# RF-antenna.net
KiCad netlist of a schematic drawn in EAGLE
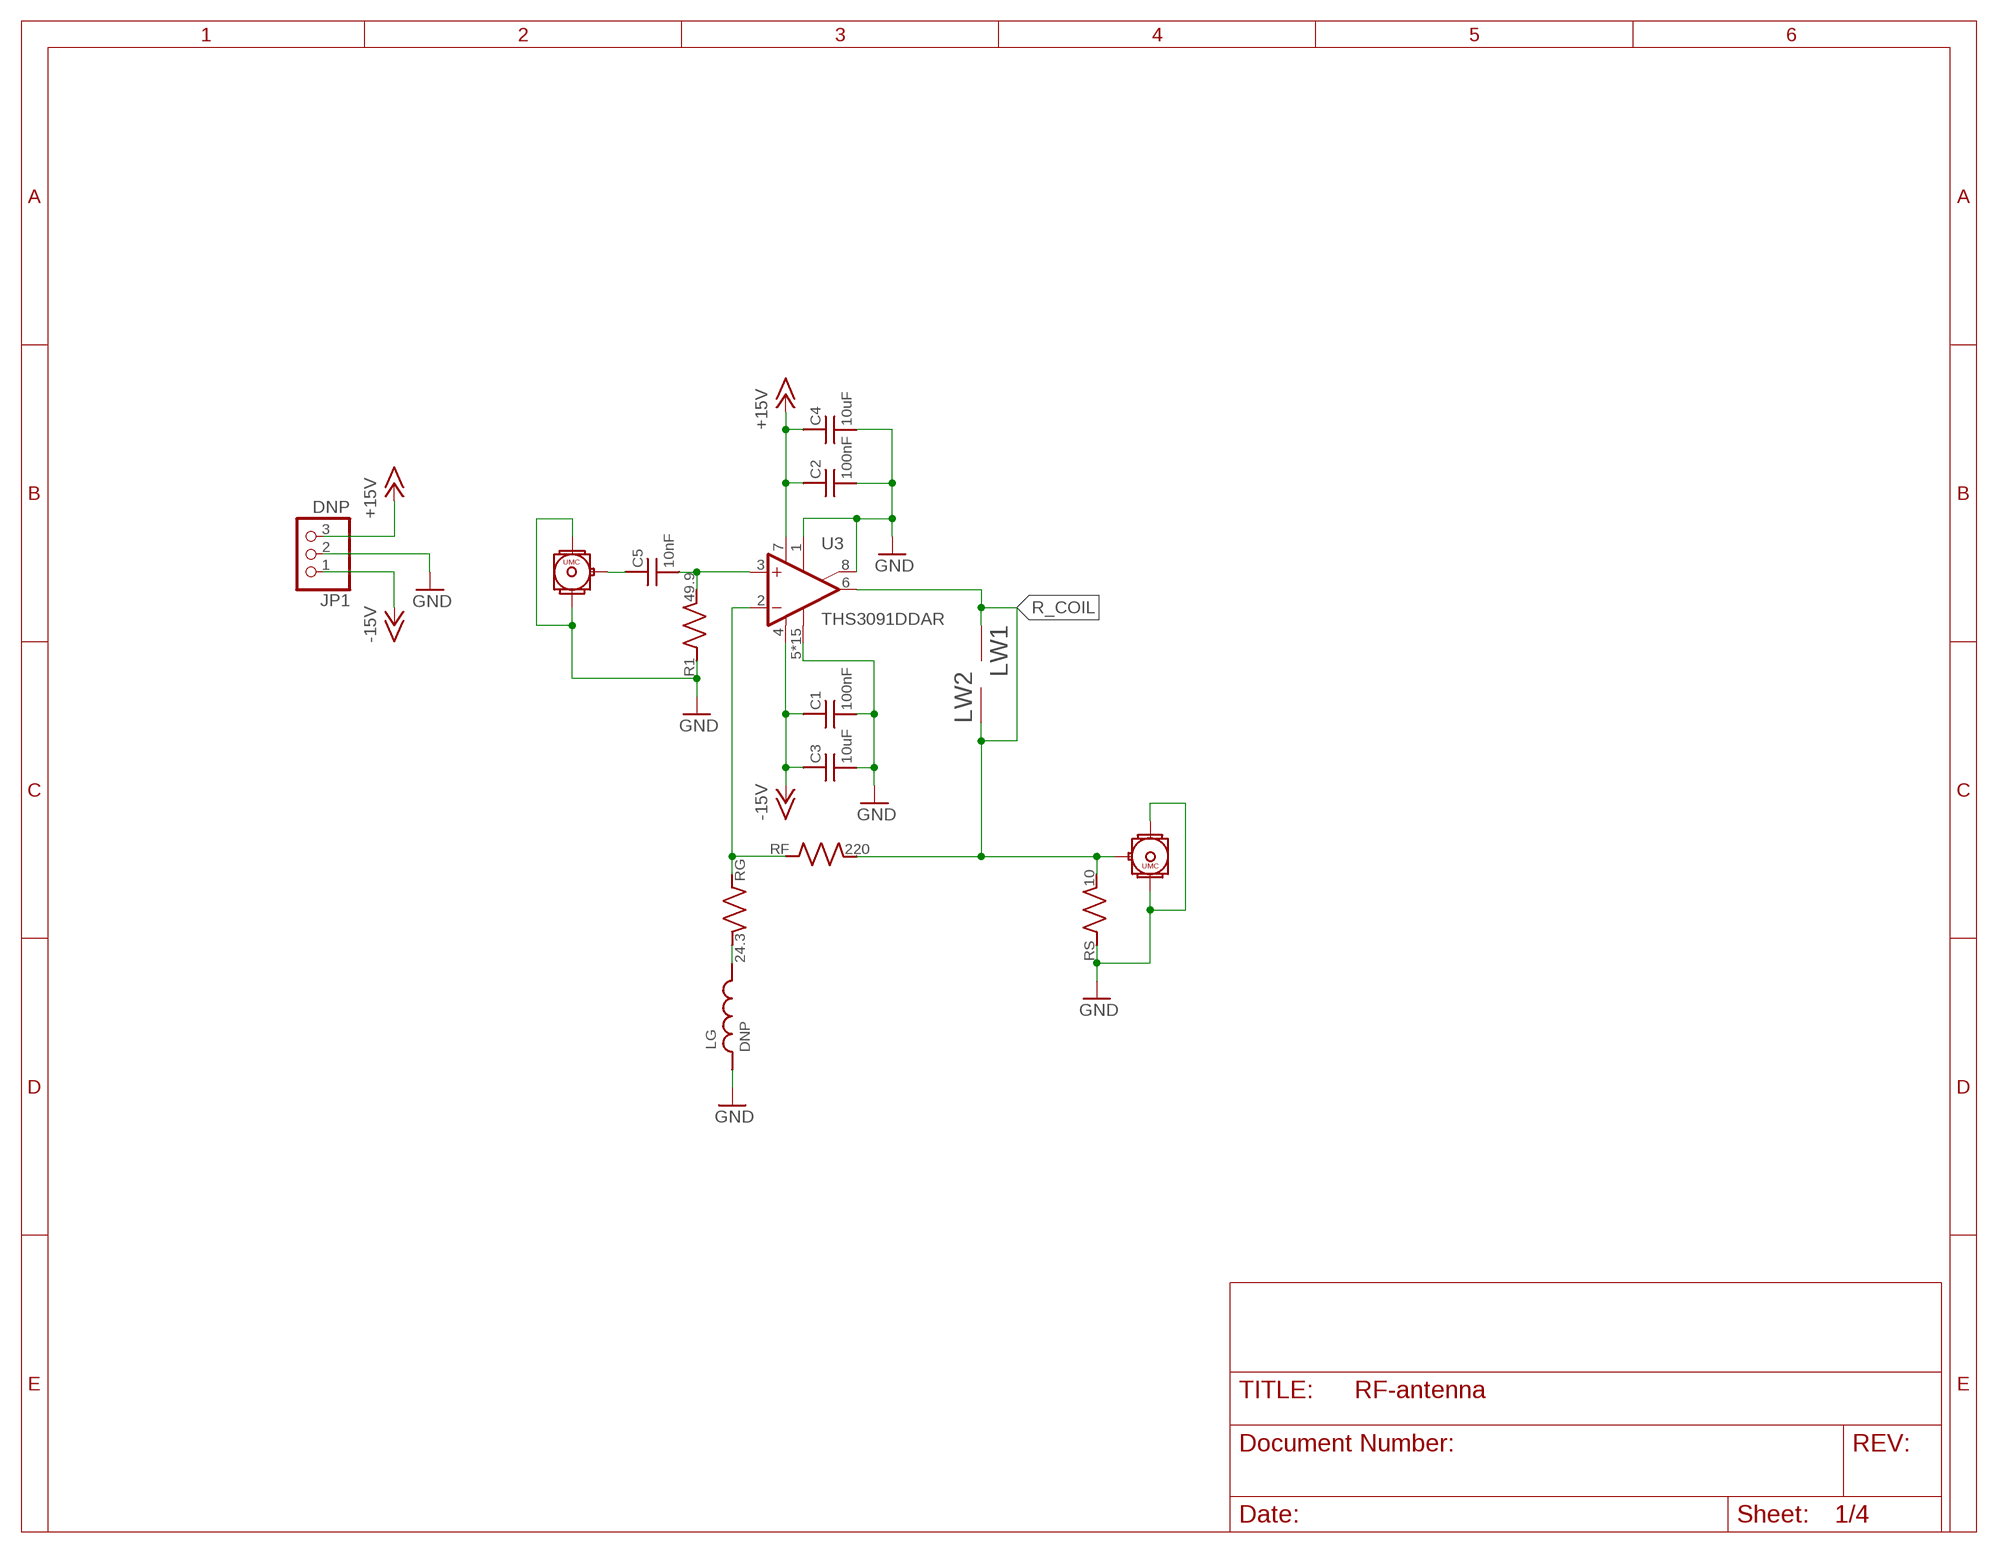
[diagram p0: schematic, sheet 1]
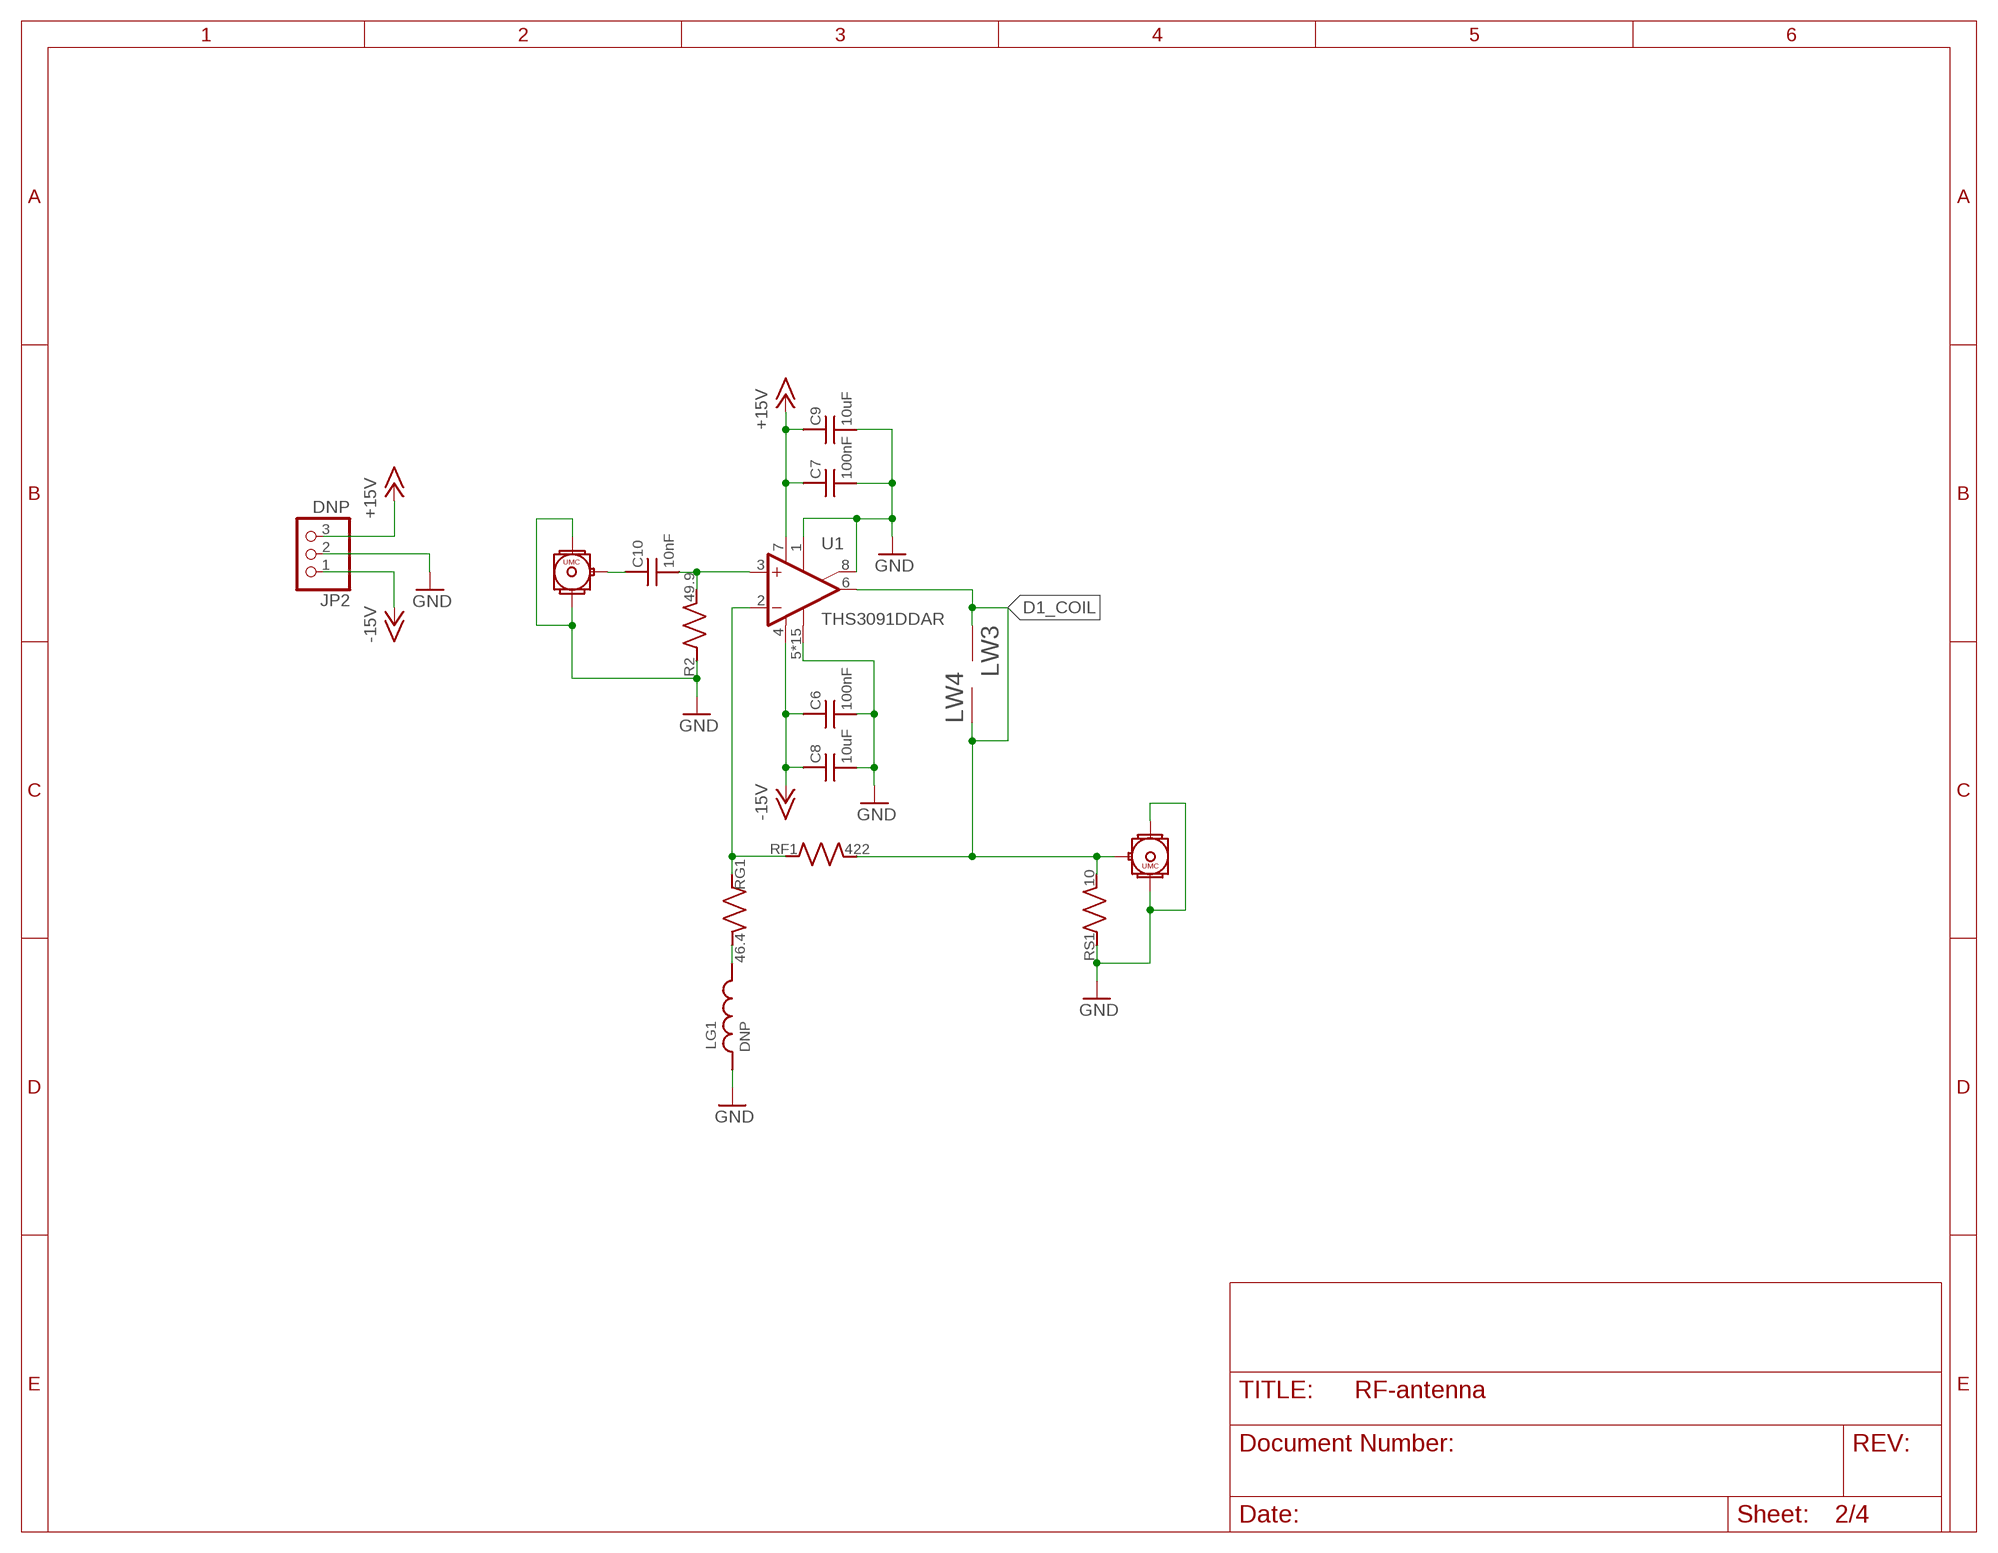
[diagram p1: schematic, sheet 2]
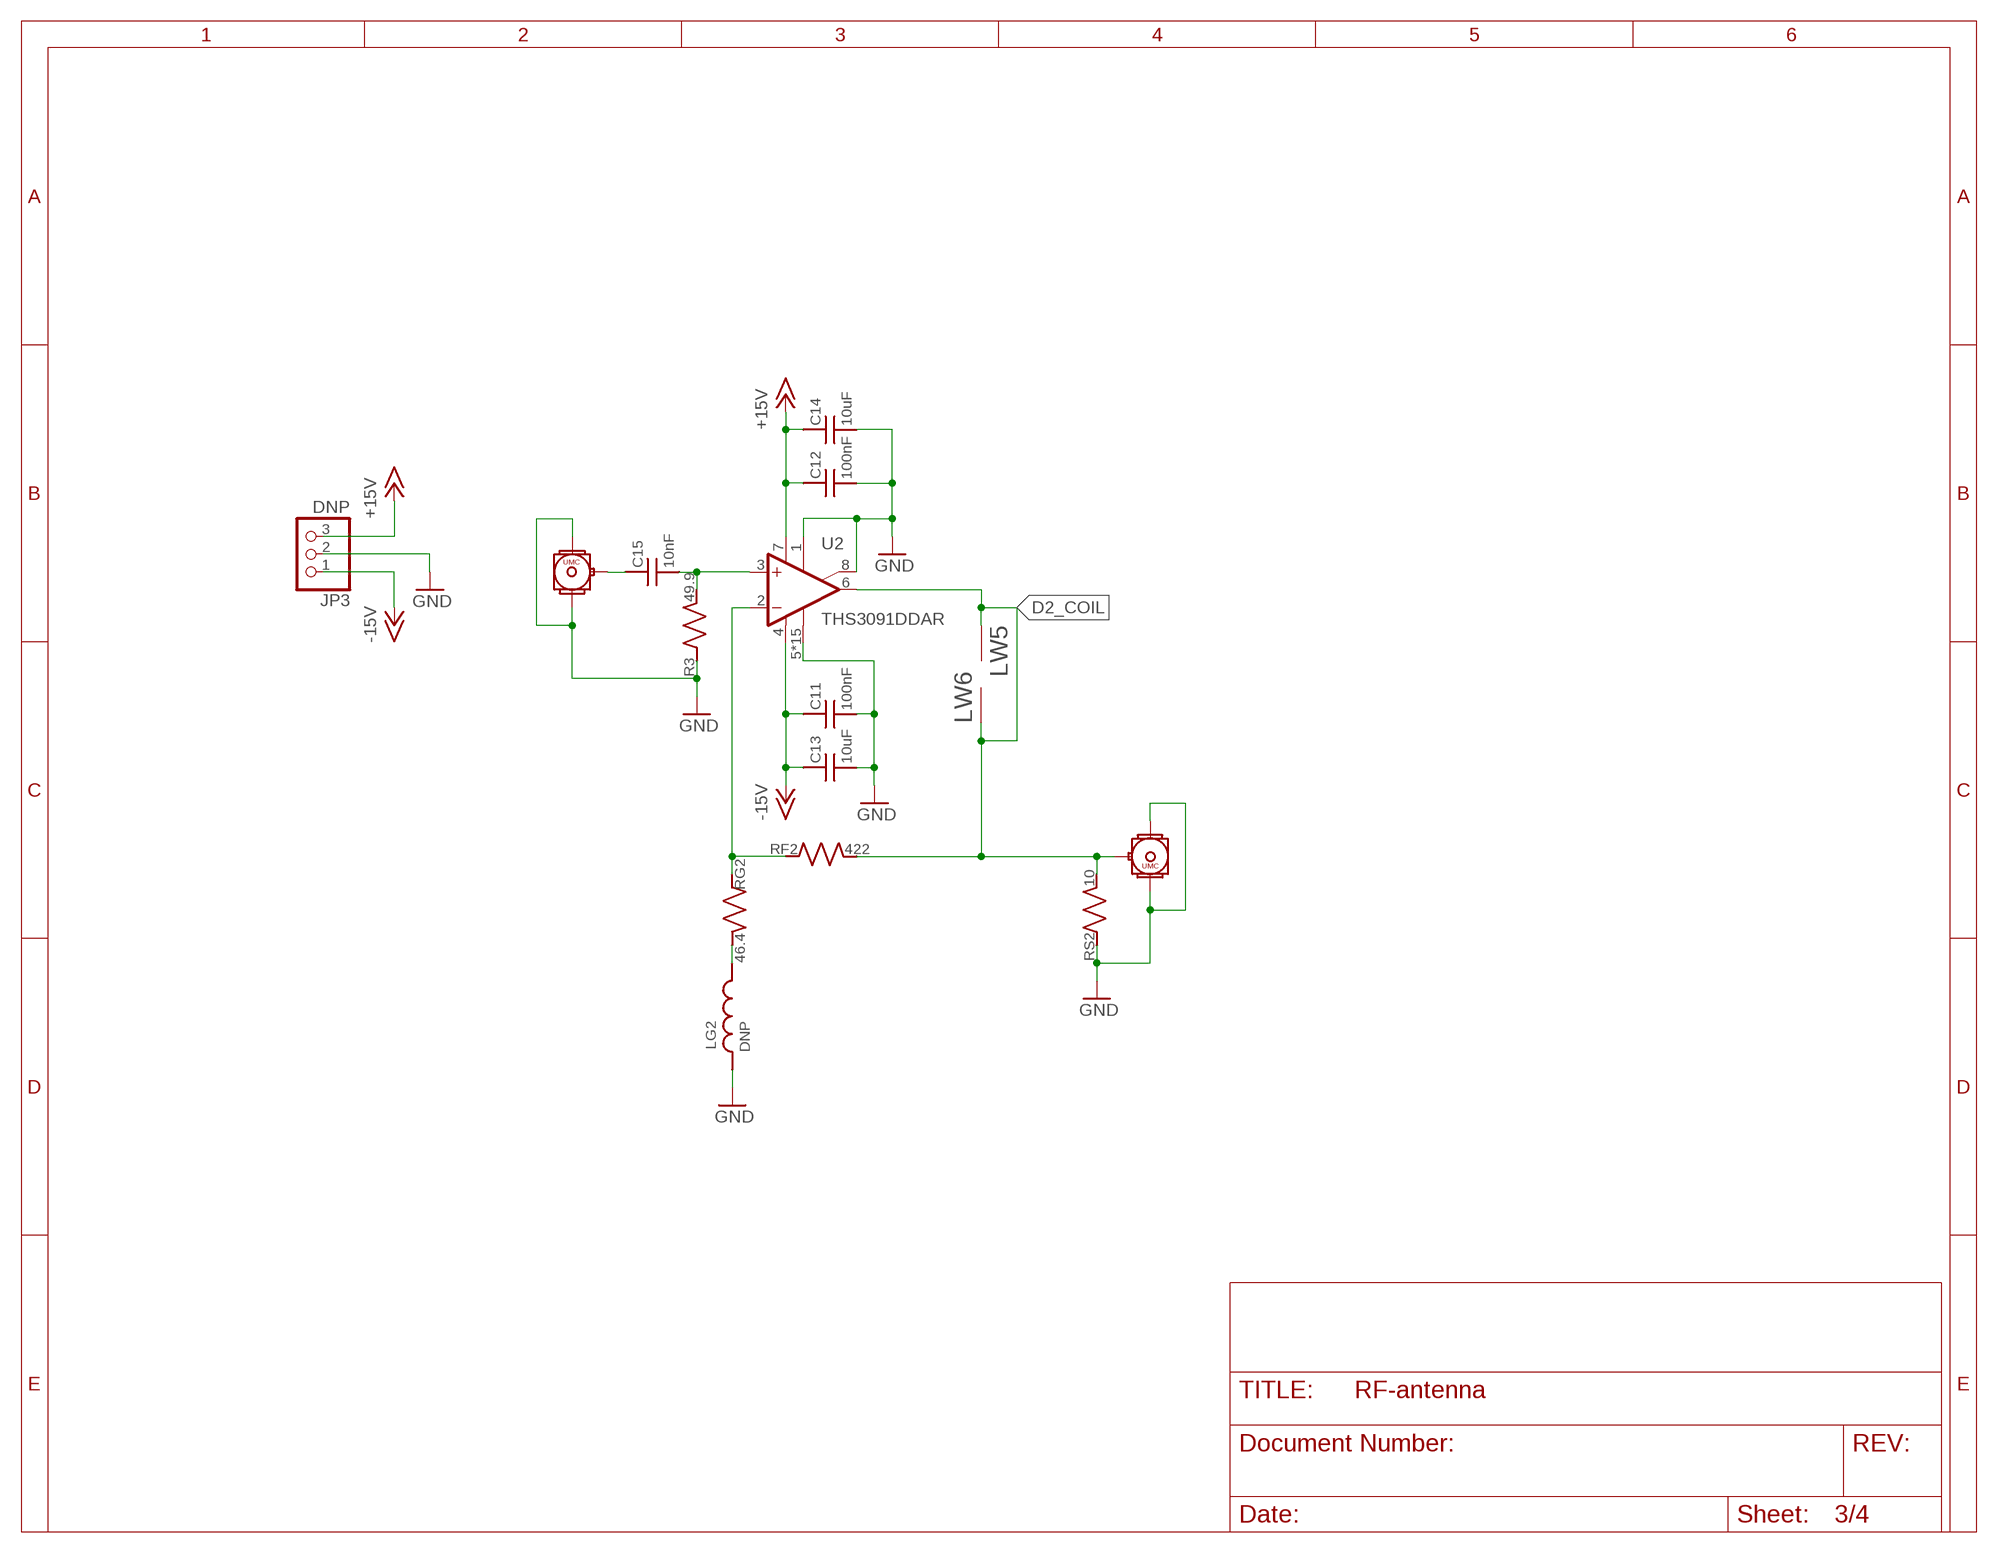
[diagram p2: schematic, sheet 3]
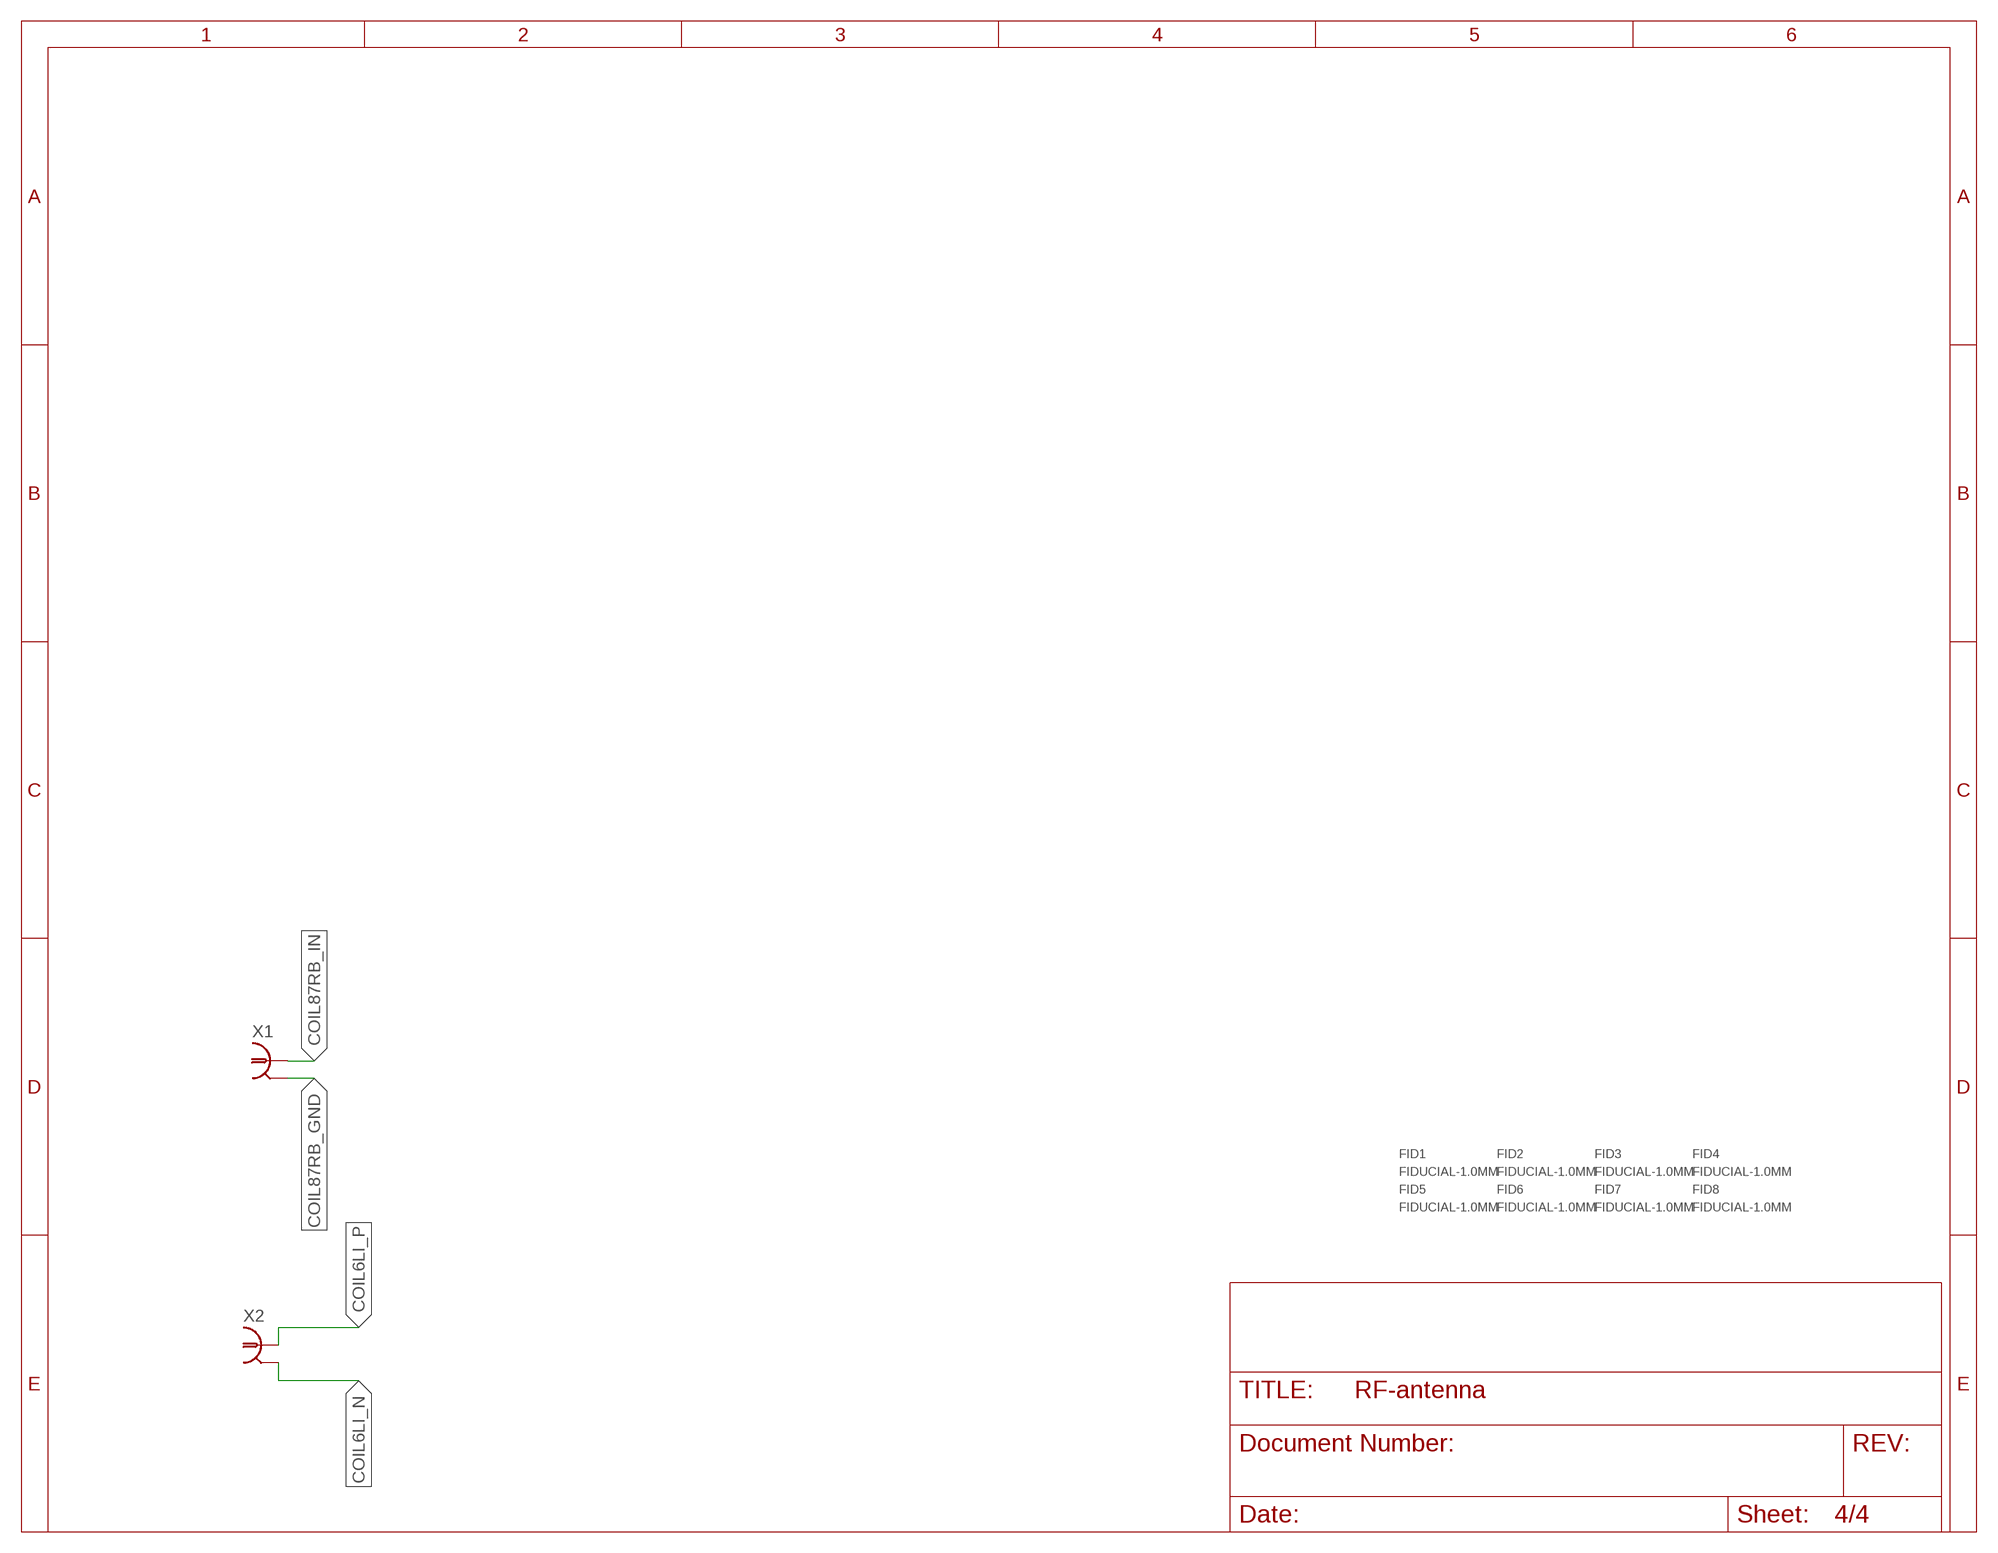
[diagram p3: schematic, sheet 4]

(export (version "E")
  (design (tool "Eeschema 10.0.6"))
  (components
    (comp (ref "C1")
      (value "100nF")
      (footprint "eagle-import:C_MLCC_0603")
      (fields (field (name "PARTNO") "06035C104K4Z2A"))
      (libsource (lib "eagle-import") (part "C_MLCC_SMDCMLCC_0603"))
    )
    (comp (ref "C2")
      (value "100nF")
      (footprint "eagle-import:C_MLCC_0603")
      (fields (field (name "PARTNO") "06035C104K4Z2A"))
      (libsource (lib "eagle-import") (part "C_MLCC_SMDCMLCC_0603"))
    )
    (comp (ref "C3")
      (value "10uF")
      (footprint "eagle-import:C_MLCC_1206")
      (fields (field (name "PARTNO") "CL31A106MBHNNNE"))
      (libsource (lib "eagle-import") (part "C_MLCC_SMDCMLCC_1206"))
    )
    (comp (ref "C4")
      (value "10uF")
      (footprint "eagle-import:C_MLCC_1206")
      (fields (field (name "PARTNO") "CL31A106MBHNNNE"))
      (libsource (lib "eagle-import") (part "C_MLCC_SMDCMLCC_1206"))
    )
    (comp (ref "C5")
      (value "10nF")
      (footprint "eagle-import:C_MLCC_0402")
      (fields (field (name "PARTNO") "CL05B103KB5NNNC"))
      (libsource (lib "eagle-import") (part "C_MLCC_SMDCMLCC_0402"))
    )
    (comp (ref "CON1")
      (value "UMC_CONNECTORREGULAR")
      (footprint "eagle-import:UMC_CONNECTOR")
      (fields (field (name "PARTNO") "1909763-1"))
      (libsource (lib "eagle-import") (part "UMC_CONNECTORREGULAR"))
    )
    (comp (ref "CON2")
      (value "UMC_CONNECTORREGULAR")
      (footprint "eagle-import:UMC_CONNECTOR")
      (fields (field (name "PARTNO") "1909763-1"))
      (libsource (lib "eagle-import") (part "UMC_CONNECTORREGULAR"))
    )
    (comp (ref "JP1")
      (value "DNP")
      (footprint "eagle-import:1X03")
      (fields (field (name "PARTNO") "640456-3"))
      (libsource (lib "eagle-import") (part "PINHD-1X3"))
    )
    (comp (ref "LG")
      (value "DNP")
      (footprint "eagle-import:1008")
      (libsource (lib "eagle-import") (part "L_FERRITE_SMD_1008"))
    )
    (comp (ref "LW1")
      (value "LITZ_TERM")
      (footprint "eagle-import:LITZ_100MHZ")
      (libsource (lib "eagle-import") (part "LITZ_TERM"))
    )
    (comp (ref "LW2")
      (value "LITZ_TERM")
      (footprint "eagle-import:LITZ_100MHZ")
      (libsource (lib "eagle-import") (part "LITZ_TERM"))
    )
    (comp (ref "R1")
      (value "49.9")
      (footprint "eagle-import:R_0402")
      (fields (field (name "PARTNO") "ERA-2AEB49R9X"))
      (libsource (lib "eagle-import") (part "R_SMDR0402"))
    )
    (comp (ref "RF")
      (value "220")
      (footprint "eagle-import:R_0603")
      (fields (field (name "PARTNO") "TNPW0603220RBEEA"))
      (libsource (lib "eagle-import") (part "R_SMDR0603"))
    )
    (comp (ref "RG")
      (value "24.3")
      (footprint "eagle-import:R_0402")
      (fields (field (name "PARTNO") "RP73PF1E24R3BTD"))
      (libsource (lib "eagle-import") (part "R_SMDR0402"))
    )
    (comp (ref "RS")
      (value "10")
      (footprint "eagle-import:R_1206")
      (fields (field (name "PARTNO") "PHP01206E10R0BST5"))
      (libsource (lib "eagle-import") (part "R_SMDR1206"))
    )
    (comp (ref "U3")
      (value "THS3091DDAR")
      (footprint "eagle-import:DDA8_2P28X2P28")
      (fields (field (name "MANUFACTURER") "Texas Instruments"))
      (libsource (lib "eagle-import") (part "THS3091DDAR"))
    )
    (comp (ref "FID1")
      (value "FIDUCIAL-1.0MM")
      (footprint "eagle-import:FID_1.0MM")
      (libsource (lib "eagle-import") (part "FIDUCIAL-1.0MM"))
    )
    (comp (ref "FID2")
      (value "FIDUCIAL-1.0MM")
      (footprint "eagle-import:FID_1.0MM")
      (libsource (lib "eagle-import") (part "FIDUCIAL-1.0MM"))
    )
    (comp (ref "FID3")
      (value "FIDUCIAL-1.0MM")
      (footprint "eagle-import:FID_1.0MM")
      (libsource (lib "eagle-import") (part "FIDUCIAL-1.0MM"))
    )
    (comp (ref "FID4")
      (value "FIDUCIAL-1.0MM")
      (footprint "eagle-import:FID_1.0MM")
      (libsource (lib "eagle-import") (part "FIDUCIAL-1.0MM"))
    )
    (comp (ref "FID5")
      (value "FIDUCIAL-1.0MM")
      (footprint "eagle-import:FID_1.0MM")
      (libsource (lib "eagle-import") (part "FIDUCIAL-1.0MM"))
    )
    (comp (ref "FID6")
      (value "FIDUCIAL-1.0MM")
      (footprint "eagle-import:FID_1.0MM")
      (libsource (lib "eagle-import") (part "FIDUCIAL-1.0MM"))
    )
    (comp (ref "FID7")
      (value "FIDUCIAL-1.0MM")
      (footprint "eagle-import:FID_1.0MM")
      (libsource (lib "eagle-import") (part "FIDUCIAL-1.0MM"))
    )
    (comp (ref "FID8")
      (value "FIDUCIAL-1.0MM")
      (footprint "eagle-import:FID_1.0MM")
      (libsource (lib "eagle-import") (part "FIDUCIAL-1.0MM"))
    )
    (comp (ref "X1")
      (value "SMA-V")
      (footprint "eagle-import:SMA-V")
      (fields (field (name "PARTNO") "5-1814832-1"))
      (libsource (lib "eagle-import") (part "SMA-V"))
    )
    (comp (ref "X2")
      (value "SMA-V")
      (footprint "eagle-import:SMA-V")
      (fields (field (name "PARTNO") "5-1814832-1"))
      (libsource (lib "eagle-import") (part "SMA-V"))
    )
    (comp (ref "C11")
      (value "100nF")
      (footprint "eagle-import:C_MLCC_0603")
      (fields (field (name "PARTNO") "06035C104K4Z2A"))
      (libsource (lib "eagle-import") (part "C_MLCC_SMDCMLCC_0603"))
    )
    (comp (ref "C12")
      (value "100nF")
      (footprint "eagle-import:C_MLCC_0603")
      (fields (field (name "PARTNO") "06035C104K4Z2A"))
      (libsource (lib "eagle-import") (part "C_MLCC_SMDCMLCC_0603"))
    )
    (comp (ref "C13")
      (value "10uF")
      (footprint "eagle-import:C_MLCC_1206")
      (fields (field (name "PARTNO") "CL31A106MBHNNNE"))
      (libsource (lib "eagle-import") (part "C_MLCC_SMDCMLCC_1206"))
    )
    (comp (ref "C14")
      (value "10uF")
      (footprint "eagle-import:C_MLCC_1206")
      (fields (field (name "PARTNO") "CL31A106MBHNNNE"))
      (libsource (lib "eagle-import") (part "C_MLCC_SMDCMLCC_1206"))
    )
    (comp (ref "C15")
      (value "10nF")
      (footprint "eagle-import:C_MLCC_0402")
      (fields (field (name "PARTNO") "CL05B103KB5NNNC"))
      (libsource (lib "eagle-import") (part "C_MLCC_SMDCMLCC_0402"))
    )
    (comp (ref "CON5")
      (value "UMC_CONNECTORREGULAR")
      (footprint "eagle-import:UMC_CONNECTOR")
      (fields (field (name "PARTNO") "1909763-1"))
      (libsource (lib "eagle-import") (part "UMC_CONNECTORREGULAR"))
    )
    (comp (ref "CON6")
      (value "UMC_CONNECTORREGULAR")
      (footprint "eagle-import:UMC_CONNECTOR")
      (fields (field (name "PARTNO") "1909763-1"))
      (libsource (lib "eagle-import") (part "UMC_CONNECTORREGULAR"))
    )
    (comp (ref "JP3")
      (value "DNP")
      (footprint "eagle-import:1X03")
      (fields (field (name "PARTNO") "640456-3"))
      (libsource (lib "eagle-import") (part "PINHD-1X3"))
    )
    (comp (ref "LG2")
      (value "DNP")
      (footprint "eagle-import:1008")
      (libsource (lib "eagle-import") (part "L_FERRITE_SMD_1008"))
    )
    (comp (ref "LW5")
      (value "LITZ_TERM")
      (footprint "eagle-import:LITZ_100MHZ")
      (libsource (lib "eagle-import") (part "LITZ_TERM"))
    )
    (comp (ref "LW6")
      (value "LITZ_TERM")
      (footprint "eagle-import:LITZ_100MHZ")
      (libsource (lib "eagle-import") (part "LITZ_TERM"))
    )
    (comp (ref "R3")
      (value "49.9")
      (footprint "eagle-import:R_0402")
      (fields (field (name "PARTNO") "ERA-2AEB49R9X"))
      (libsource (lib "eagle-import") (part "R_SMDR0402"))
    )
    (comp (ref "RF2")
      (value "422")
      (footprint "eagle-import:R_0603")
      (fields (field (name "PARTNO") "TNPW0603422RBEEA"))
      (libsource (lib "eagle-import") (part "R_SMDR0603"))
    )
    (comp (ref "RG2")
      (value "46.4")
      (footprint "eagle-import:R_0402")
      (fields (field (name "PARTNO") "RP73PF1E46R4BTD"))
      (libsource (lib "eagle-import") (part "R_SMDR0402"))
    )
    (comp (ref "RS2")
      (value "10")
      (footprint "eagle-import:R_1206")
      (fields (field (name "PARTNO") "PHP01206E10R0BST5"))
      (libsource (lib "eagle-import") (part "R_SMDR1206"))
    )
    (comp (ref "U2")
      (value "THS3091DDAR")
      (footprint "eagle-import:DDA8_2P28X2P28")
      (fields (field (name "MANUFACTURER") "Texas Instruments"))
      (libsource (lib "eagle-import") (part "THS3091DDAR"))
    )
    (comp (ref "C6")
      (value "100nF")
      (footprint "eagle-import:C_MLCC_0603")
      (fields (field (name "PARTNO") "06035C104K4Z2A"))
      (libsource (lib "eagle-import") (part "C_MLCC_SMDCMLCC_0603"))
    )
    (comp (ref "C7")
      (value "100nF")
      (footprint "eagle-import:C_MLCC_0603")
      (fields (field (name "PARTNO") "06035C104K4Z2A"))
      (libsource (lib "eagle-import") (part "C_MLCC_SMDCMLCC_0603"))
    )
    (comp (ref "C8")
      (value "10uF")
      (footprint "eagle-import:C_MLCC_1206")
      (fields (field (name "PARTNO") "CL31A106MBHNNNE"))
      (libsource (lib "eagle-import") (part "C_MLCC_SMDCMLCC_1206"))
    )
    (comp (ref "C9")
      (value "10uF")
      (footprint "eagle-import:C_MLCC_1206")
      (fields (field (name "PARTNO") "CL31A106MBHNNNE"))
      (libsource (lib "eagle-import") (part "C_MLCC_SMDCMLCC_1206"))
    )
    (comp (ref "C10")
      (value "10nF")
      (footprint "eagle-import:C_MLCC_0402")
      (fields (field (name "PARTNO") "CL05B103KB5NNNC"))
      (libsource (lib "eagle-import") (part "C_MLCC_SMDCMLCC_0402"))
    )
    (comp (ref "CON3")
      (value "UMC_CONNECTORREGULAR")
      (footprint "eagle-import:UMC_CONNECTOR")
      (fields (field (name "PARTNO") "1909763-1"))
      (libsource (lib "eagle-import") (part "UMC_CONNECTORREGULAR"))
    )
    (comp (ref "CON4")
      (value "UMC_CONNECTORREGULAR")
      (footprint "eagle-import:UMC_CONNECTOR")
      (fields (field (name "PARTNO") "1909763-1"))
      (libsource (lib "eagle-import") (part "UMC_CONNECTORREGULAR"))
    )
    (comp (ref "JP2")
      (value "DNP")
      (footprint "eagle-import:1X03")
      (fields (field (name "PARTNO") "640456-3"))
      (libsource (lib "eagle-import") (part "PINHD-1X3"))
    )
    (comp (ref "LG1")
      (value "DNP")
      (footprint "eagle-import:1008")
      (libsource (lib "eagle-import") (part "L_FERRITE_SMD_1008"))
    )
    (comp (ref "LW3")
      (value "LITZ_TERM")
      (footprint "eagle-import:LITZ_100MHZ")
      (libsource (lib "eagle-import") (part "LITZ_TERM"))
    )
    (comp (ref "LW4")
      (value "LITZ_TERM")
      (footprint "eagle-import:LITZ_100MHZ")
      (libsource (lib "eagle-import") (part "LITZ_TERM"))
    )
    (comp (ref "R2")
      (value "49.9")
      (footprint "eagle-import:R_0402")
      (fields (field (name "PARTNO") "ERA-2AEB49R9X"))
      (libsource (lib "eagle-import") (part "R_SMDR0402"))
    )
    (comp (ref "RF1")
      (value "422")
      (footprint "eagle-import:R_0603")
      (fields (field (name "PARTNO") "TNPW0603422RBEEA"))
      (libsource (lib "eagle-import") (part "R_SMDR0603"))
    )
    (comp (ref "RG1")
      (value "46.4")
      (footprint "eagle-import:R_0402")
      (fields (field (name "PARTNO") "RP73PF1E46R4BTD"))
      (libsource (lib "eagle-import") (part "R_SMDR0402"))
    )
    (comp (ref "RS1")
      (value "10")
      (footprint "eagle-import:R_1206")
      (fields (field (name "PARTNO") "PHP01206E10R0BST5"))
      (libsource (lib "eagle-import") (part "R_SMDR1206"))
    )
    (comp (ref "U1")
      (value "THS3091DDAR")
      (footprint "eagle-import:DDA8_2P28X2P28")
      (fields (field (name "MANUFACTURER") "Texas Instruments"))
      (libsource (lib "eagle-import") (part "THS3091DDAR"))
    )
  )
  (nets
    (net (code "1") (name "+15V") (class "Default")
      (node (ref "C12") (pin "P$1") (pinfunction "1_P$1") (pintype "passive"))
      (node (ref "C14") (pin "P$1") (pinfunction "1_P$1") (pintype "passive"))
      (node (ref "C2") (pin "P$1") (pinfunction "1_P$1") (pintype "passive"))
      (node (ref "C4") (pin "P$1") (pinfunction "1_P$1") (pintype "passive"))
      (node (ref "C7") (pin "P$1") (pinfunction "1_P$1") (pintype "passive"))
      (node (ref "C9") (pin "P$1") (pinfunction "1_P$1") (pintype "passive"))
      (node (ref "JP1") (pin "3") (pinfunction "3_3") (pintype "passive"))
      (node (ref "JP2") (pin "3") (pinfunction "3_3") (pintype "passive"))
      (node (ref "JP3") (pin "3") (pinfunction "3_3") (pintype "passive"))
      (node (ref "U1") (pin "7") (pinfunction "V+_7") (pintype "power_in"))
      (node (ref "U2") (pin "7") (pinfunction "V+_7") (pintype "power_in"))
      (node (ref "U3") (pin "7") (pinfunction "V+_7") (pintype "power_in"))
    )
    (net (code "2") (name "-15V") (class "Default")
      (node (ref "C1") (pin "P$1") (pinfunction "1_P$1") (pintype "passive"))
      (node (ref "C11") (pin "P$1") (pinfunction "1_P$1") (pintype "passive"))
      (node (ref "C13") (pin "P$1") (pinfunction "1_P$1") (pintype "passive"))
      (node (ref "C3") (pin "P$1") (pinfunction "1_P$1") (pintype "passive"))
      (node (ref "C6") (pin "P$1") (pinfunction "1_P$1") (pintype "passive"))
      (node (ref "C8") (pin "P$1") (pinfunction "1_P$1") (pintype "passive"))
      (node (ref "JP1") (pin "1") (pinfunction "1_1") (pintype "passive"))
      (node (ref "JP2") (pin "1") (pinfunction "1_1") (pintype "passive"))
      (node (ref "JP3") (pin "1") (pinfunction "1_1") (pintype "passive"))
      (node (ref "U1") (pin "4") (pinfunction "V-_4") (pintype "power_in"))
      (node (ref "U2") (pin "4") (pinfunction "V-_4") (pintype "power_in"))
      (node (ref "U3") (pin "4") (pinfunction "V-_4") (pintype "power_in"))
    )
    (net (code "3") (name "COIL6LI_N") (class "Default")
      (node (ref "X2") (pin "GND1") (pinfunction "2_GND1") (pintype "passive"))
      (node (ref "X2") (pin "GND2") (pinfunction "2_GND2") (pintype "passive"))
      (node (ref "X2") (pin "GND3") (pinfunction "2_GND3") (pintype "passive"))
      (node (ref "X2") (pin "GND4") (pinfunction "2_GND4") (pintype "passive"))
    )
    (net (code "4") (name "COIL6LI_P") (class "Default")
      (node (ref "X2") (pin "RF") (pinfunction "1_RF") (pintype "passive"))
    )
    (net (code "5") (name "COIL87RB_GND") (class "Default")
      (node (ref "X1") (pin "GND1") (pinfunction "2_GND1") (pintype "passive"))
      (node (ref "X1") (pin "GND2") (pinfunction "2_GND2") (pintype "passive"))
      (node (ref "X1") (pin "GND3") (pinfunction "2_GND3") (pintype "passive"))
      (node (ref "X1") (pin "GND4") (pinfunction "2_GND4") (pintype "passive"))
    )
    (net (code "6") (name "COIL87RB_IN") (class "Default")
      (node (ref "X1") (pin "RF") (pinfunction "1_RF") (pintype "passive"))
    )
    (net (code "7") (name "D1_COIL") (class "Default")
      (node (ref "CON4") (pin "P$1") (pinfunction "P$1_P$1") (pintype "bidirectional"))
      (node (ref "LW3") (pin "T1") (pinfunction "P1_T1") (pintype "passive"))
      (node (ref "LW4") (pin "T1") (pinfunction "P1_T1") (pintype "passive"))
      (node (ref "RF1") (pin "P$2") (pinfunction "2_P$2") (pintype "passive"))
      (node (ref "RS1") (pin "P$2") (pinfunction "2_P$2") (pintype "passive"))
      (node (ref "U1") (pin "6") (pinfunction "OUT_6") (pintype "output"))
    )
    (net (code "8") (name "D2_COIL") (class "Default")
      (node (ref "CON6") (pin "P$1") (pinfunction "P$1_P$1") (pintype "bidirectional"))
      (node (ref "LW5") (pin "T1") (pinfunction "P1_T1") (pintype "passive"))
      (node (ref "LW6") (pin "T1") (pinfunction "P1_T1") (pintype "passive"))
      (node (ref "RF2") (pin "P$2") (pinfunction "2_P$2") (pintype "passive"))
      (node (ref "RS2") (pin "P$2") (pinfunction "2_P$2") (pintype "passive"))
      (node (ref "U2") (pin "6") (pinfunction "OUT_6") (pintype "output"))
    )
    (net (code "9") (name "GND") (class "Default")
      (node (ref "C1") (pin "P$2") (pinfunction "2_P$2") (pintype "passive"))
      (node (ref "C11") (pin "P$2") (pinfunction "2_P$2") (pintype "passive"))
      (node (ref "C12") (pin "P$2") (pinfunction "2_P$2") (pintype "passive"))
      (node (ref "C13") (pin "P$2") (pinfunction "2_P$2") (pintype "passive"))
      (node (ref "C14") (pin "P$2") (pinfunction "2_P$2") (pintype "passive"))
      (node (ref "C2") (pin "P$2") (pinfunction "2_P$2") (pintype "passive"))
      (node (ref "C3") (pin "P$2") (pinfunction "2_P$2") (pintype "passive"))
      (node (ref "C4") (pin "P$2") (pinfunction "2_P$2") (pintype "passive"))
      (node (ref "C6") (pin "P$2") (pinfunction "2_P$2") (pintype "passive"))
      (node (ref "C7") (pin "P$2") (pinfunction "2_P$2") (pintype "passive"))
      (node (ref "C8") (pin "P$2") (pinfunction "2_P$2") (pintype "passive"))
      (node (ref "C9") (pin "P$2") (pinfunction "2_P$2") (pintype "passive"))
      (node (ref "CON1") (pin "P$2") (pinfunction "P$2_P$2") (pintype "bidirectional"))
      (node (ref "CON1") (pin "P$3") (pinfunction "P$3_P$3") (pintype "bidirectional"))
      (node (ref "CON2") (pin "P$2") (pinfunction "P$2_P$2") (pintype "bidirectional"))
      (node (ref "CON2") (pin "P$3") (pinfunction "P$3_P$3") (pintype "bidirectional"))
      (node (ref "CON3") (pin "P$2") (pinfunction "P$2_P$2") (pintype "bidirectional"))
      (node (ref "CON3") (pin "P$3") (pinfunction "P$3_P$3") (pintype "bidirectional"))
      (node (ref "CON4") (pin "P$2") (pinfunction "P$2_P$2") (pintype "bidirectional"))
      (node (ref "CON4") (pin "P$3") (pinfunction "P$3_P$3") (pintype "bidirectional"))
      (node (ref "CON5") (pin "P$2") (pinfunction "P$2_P$2") (pintype "bidirectional"))
      (node (ref "CON5") (pin "P$3") (pinfunction "P$3_P$3") (pintype "bidirectional"))
      (node (ref "CON6") (pin "P$2") (pinfunction "P$2_P$2") (pintype "bidirectional"))
      (node (ref "CON6") (pin "P$3") (pinfunction "P$3_P$3") (pintype "bidirectional"))
      (node (ref "JP1") (pin "2") (pinfunction "2_2") (pintype "passive"))
      (node (ref "JP2") (pin "2") (pinfunction "2_2") (pintype "passive"))
      (node (ref "JP3") (pin "2") (pinfunction "2_2") (pintype "passive"))
      (node (ref "LG") (pin "P$1") (pinfunction "1_P$1") (pintype "passive"))
      (node (ref "LG1") (pin "P$1") (pinfunction "1_P$1") (pintype "passive"))
      (node (ref "LG2") (pin "P$1") (pinfunction "1_P$1") (pintype "passive"))
      (node (ref "R1") (pin "P$1") (pinfunction "1_P$1") (pintype "passive"))
      (node (ref "R2") (pin "P$1") (pinfunction "1_P$1") (pintype "passive"))
      (node (ref "R3") (pin "P$1") (pinfunction "1_P$1") (pintype "passive"))
      (node (ref "RS") (pin "P$1") (pinfunction "1_P$1") (pintype "passive"))
      (node (ref "RS1") (pin "P$1") (pinfunction "1_P$1") (pintype "passive"))
      (node (ref "RS2") (pin "P$1") (pinfunction "1_P$1") (pintype "passive"))
      (node (ref "U1") (pin "1") (pinfunction "ON1_1") (pintype "passive"))
      (node (ref "U1") (pin "5") (pinfunction "OPT_5") (pintype "passive"))
      (node (ref "U1") (pin "8") (pinfunction "ON2_8") (pintype "passive"))
      (node (ref "U1") (pin "EPAD") (pinfunction "OPT_EPAD") (pintype "passive"))
      (node (ref "U1") (pin "P$1") (pinfunction "OPT_P$1") (pintype "passive"))
      (node (ref "U1") (pin "P$10") (pinfunction "OPT_P$10") (pintype "passive"))
      (node (ref "U1") (pin "P$11") (pinfunction "OPT_P$11") (pintype "passive"))
      (node (ref "U1") (pin "P$12") (pinfunction "OPT_P$12") (pintype "passive"))
      (node (ref "U1") (pin "P$13") (pinfunction "OPT_P$13") (pintype "passive"))
      (node (ref "U1") (pin "P$2") (pinfunction "OPT_P$2") (pintype "passive"))
      (node (ref "U1") (pin "P$3") (pinfunction "OPT_P$3") (pintype "passive"))
      (node (ref "U1") (pin "P$4") (pinfunction "OPT_P$4") (pintype "passive"))
      (node (ref "U1") (pin "P$5") (pinfunction "OPT_P$5") (pintype "passive"))
      (node (ref "U1") (pin "P$6") (pinfunction "OPT_P$6") (pintype "passive"))
      (node (ref "U1") (pin "P$7") (pinfunction "OPT_P$7") (pintype "passive"))
      (node (ref "U1") (pin "P$8") (pinfunction "OPT_P$8") (pintype "passive"))
      (node (ref "U1") (pin "P$9") (pinfunction "OPT_P$9") (pintype "passive"))
      (node (ref "U2") (pin "1") (pinfunction "ON1_1") (pintype "passive"))
      (node (ref "U2") (pin "5") (pinfunction "OPT_5") (pintype "passive"))
      (node (ref "U2") (pin "8") (pinfunction "ON2_8") (pintype "passive"))
      (node (ref "U2") (pin "EPAD") (pinfunction "OPT_EPAD") (pintype "passive"))
      (node (ref "U2") (pin "P$1") (pinfunction "OPT_P$1") (pintype "passive"))
      (node (ref "U2") (pin "P$10") (pinfunction "OPT_P$10") (pintype "passive"))
      (node (ref "U2") (pin "P$11") (pinfunction "OPT_P$11") (pintype "passive"))
      (node (ref "U2") (pin "P$12") (pinfunction "OPT_P$12") (pintype "passive"))
      (node (ref "U2") (pin "P$13") (pinfunction "OPT_P$13") (pintype "passive"))
      (node (ref "U2") (pin "P$2") (pinfunction "OPT_P$2") (pintype "passive"))
      (node (ref "U2") (pin "P$3") (pinfunction "OPT_P$3") (pintype "passive"))
      (node (ref "U2") (pin "P$4") (pinfunction "OPT_P$4") (pintype "passive"))
      (node (ref "U2") (pin "P$5") (pinfunction "OPT_P$5") (pintype "passive"))
      (node (ref "U2") (pin "P$6") (pinfunction "OPT_P$6") (pintype "passive"))
      (node (ref "U2") (pin "P$7") (pinfunction "OPT_P$7") (pintype "passive"))
      (node (ref "U2") (pin "P$8") (pinfunction "OPT_P$8") (pintype "passive"))
      (node (ref "U2") (pin "P$9") (pinfunction "OPT_P$9") (pintype "passive"))
      (node (ref "U3") (pin "1") (pinfunction "ON1_1") (pintype "passive"))
      (node (ref "U3") (pin "5") (pinfunction "OPT_5") (pintype "passive"))
      (node (ref "U3") (pin "8") (pinfunction "ON2_8") (pintype "passive"))
      (node (ref "U3") (pin "EPAD") (pinfunction "OPT_EPAD") (pintype "passive"))
      (node (ref "U3") (pin "P$1") (pinfunction "OPT_P$1") (pintype "passive"))
      (node (ref "U3") (pin "P$10") (pinfunction "OPT_P$10") (pintype "passive"))
      (node (ref "U3") (pin "P$11") (pinfunction "OPT_P$11") (pintype "passive"))
      (node (ref "U3") (pin "P$12") (pinfunction "OPT_P$12") (pintype "passive"))
      (node (ref "U3") (pin "P$13") (pinfunction "OPT_P$13") (pintype "passive"))
      (node (ref "U3") (pin "P$2") (pinfunction "OPT_P$2") (pintype "passive"))
      (node (ref "U3") (pin "P$3") (pinfunction "OPT_P$3") (pintype "passive"))
      (node (ref "U3") (pin "P$4") (pinfunction "OPT_P$4") (pintype "passive"))
      (node (ref "U3") (pin "P$5") (pinfunction "OPT_P$5") (pintype "passive"))
      (node (ref "U3") (pin "P$6") (pinfunction "OPT_P$6") (pintype "passive"))
      (node (ref "U3") (pin "P$7") (pinfunction "OPT_P$7") (pintype "passive"))
      (node (ref "U3") (pin "P$8") (pinfunction "OPT_P$8") (pintype "passive"))
      (node (ref "U3") (pin "P$9") (pinfunction "OPT_P$9") (pintype "passive"))
    )
    (net (code "10") (name "Net-(C5-1)") (class "Default")
      (node (ref "C5") (pin "P$1") (pinfunction "1_P$1") (pintype "passive"))
      (node (ref "CON2") (pin "P$1") (pinfunction "P$1_P$1") (pintype "bidirectional"))
    )
    (net (code "11") (name "Net-(C5-2)") (class "Default")
      (node (ref "C5") (pin "P$2") (pinfunction "2_P$2") (pintype "passive"))
      (node (ref "R1") (pin "P$2") (pinfunction "2_P$2") (pintype "passive"))
      (node (ref "U3") (pin "3") (pinfunction "+IN_3") (pintype "input"))
    )
    (net (code "12") (name "Net-(C10-1)") (class "Default")
      (node (ref "C10") (pin "P$1") (pinfunction "1_P$1") (pintype "passive"))
      (node (ref "CON3") (pin "P$1") (pinfunction "P$1_P$1") (pintype "bidirectional"))
    )
    (net (code "13") (name "Net-(C10-2)") (class "Default")
      (node (ref "C10") (pin "P$2") (pinfunction "2_P$2") (pintype "passive"))
      (node (ref "R2") (pin "P$2") (pinfunction "2_P$2") (pintype "passive"))
      (node (ref "U1") (pin "3") (pinfunction "+IN_3") (pintype "input"))
    )
    (net (code "14") (name "Net-(C15-1)") (class "Default")
      (node (ref "C15") (pin "P$1") (pinfunction "1_P$1") (pintype "passive"))
      (node (ref "CON5") (pin "P$1") (pinfunction "P$1_P$1") (pintype "bidirectional"))
    )
    (net (code "15") (name "Net-(C15-2)") (class "Default")
      (node (ref "C15") (pin "P$2") (pinfunction "2_P$2") (pintype "passive"))
      (node (ref "R3") (pin "P$2") (pinfunction "2_P$2") (pintype "passive"))
      (node (ref "U2") (pin "3") (pinfunction "+IN_3") (pintype "input"))
    )
    (net (code "16") (name "Net-(LG-2)") (class "Default")
      (node (ref "LG") (pin "P$2") (pinfunction "2_P$2") (pintype "passive"))
      (node (ref "RG") (pin "P$2") (pinfunction "2_P$2") (pintype "passive"))
    )
    (net (code "17") (name "Net-(LG1-2)") (class "Default")
      (node (ref "LG1") (pin "P$2") (pinfunction "2_P$2") (pintype "passive"))
      (node (ref "RG1") (pin "P$2") (pinfunction "2_P$2") (pintype "passive"))
    )
    (net (code "18") (name "Net-(LG2-2)") (class "Default")
      (node (ref "LG2") (pin "P$2") (pinfunction "2_P$2") (pintype "passive"))
      (node (ref "RG2") (pin "P$2") (pinfunction "2_P$2") (pintype "passive"))
    )
    (net (code "19") (name "Net-(RF-1)") (class "Default")
      (node (ref "RF") (pin "P$1") (pinfunction "1_P$1") (pintype "passive"))
      (node (ref "RG") (pin "P$1") (pinfunction "1_P$1") (pintype "passive"))
      (node (ref "U3") (pin "2") (pinfunction "-IN_2") (pintype "input"))
    )
    (net (code "20") (name "Net-(RF1-1)") (class "Default")
      (node (ref "RF1") (pin "P$1") (pinfunction "1_P$1") (pintype "passive"))
      (node (ref "RG1") (pin "P$1") (pinfunction "1_P$1") (pintype "passive"))
      (node (ref "U1") (pin "2") (pinfunction "-IN_2") (pintype "input"))
    )
    (net (code "21") (name "Net-(RF2-1)") (class "Default")
      (node (ref "RF2") (pin "P$1") (pinfunction "1_P$1") (pintype "passive"))
      (node (ref "RG2") (pin "P$1") (pinfunction "1_P$1") (pintype "passive"))
      (node (ref "U2") (pin "2") (pinfunction "-IN_2") (pintype "input"))
    )
    (net (code "22") (name "R_COIL") (class "Default")
      (node (ref "CON1") (pin "P$1") (pinfunction "P$1_P$1") (pintype "bidirectional"))
      (node (ref "LW1") (pin "T1") (pinfunction "P1_T1") (pintype "passive"))
      (node (ref "LW2") (pin "T1") (pinfunction "P1_T1") (pintype "passive"))
      (node (ref "RF") (pin "P$2") (pinfunction "2_P$2") (pintype "passive"))
      (node (ref "RS") (pin "P$2") (pinfunction "2_P$2") (pintype "passive"))
      (node (ref "U3") (pin "6") (pinfunction "OUT_6") (pintype "output"))
    )
  )
)
